# usb-lux-meter-v1.net
KiCad netlist of a schematic drawn in EAGLE
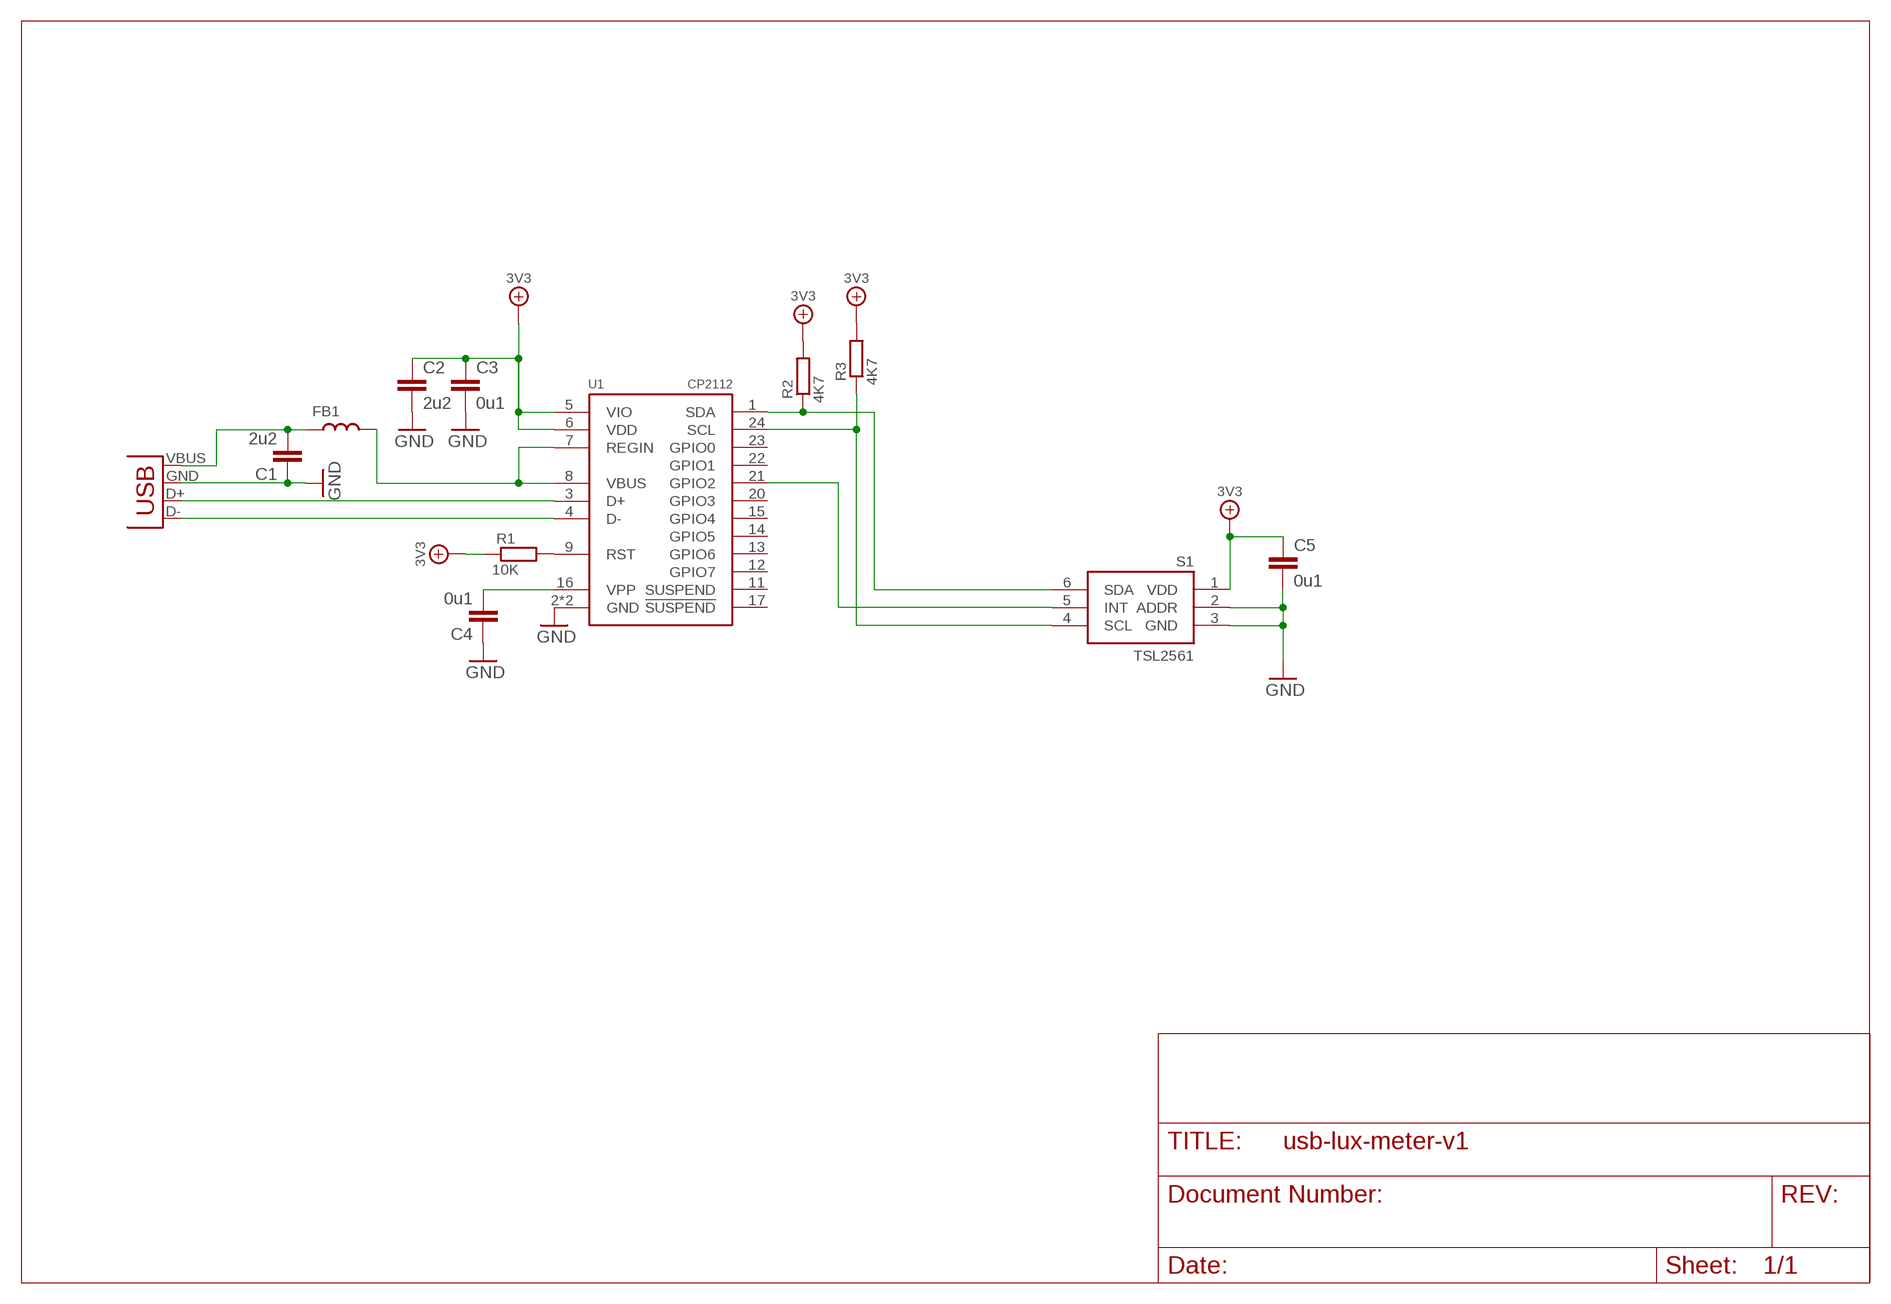
[diagram p0: schematic, sheet 1]

(export (version "E")
  (design (tool "Eeschema 10.0.6"))
  (components
    (comp (ref "C1")
      (value "2u2")
      (footprint "eagle-import:C0603")
      (libsource (lib "eagle-import") (part "CC0603"))
    )
    (comp (ref "C2")
      (value "2u2")
      (footprint "eagle-import:C0603")
      (libsource (lib "eagle-import") (part "CC0603"))
    )
    (comp (ref "C3")
      (value "0u1")
      (footprint "eagle-import:C0603")
      (libsource (lib "eagle-import") (part "CC0603"))
    )
    (comp (ref "C4")
      (value "0u1")
      (footprint "eagle-import:C0603")
      (libsource (lib "eagle-import") (part "CC0603"))
    )
    (comp (ref "C5")
      (value "0u1")
      (footprint "eagle-import:C0603")
      (libsource (lib "eagle-import") (part "CC0603"))
    )
    (comp (ref "CN1")
      (value "USB-A-H")
      (footprint "eagle-import:USB-A-H")
      (libsource (lib "eagle-import") (part "USB-A-H"))
    )
    (comp (ref "FB1")
      (value "L0603")
      (footprint "eagle-import:R603")
      (libsource (lib "eagle-import") (part "L0603"))
    )
    (comp (ref "R1")
      (value "10K")
      (footprint "eagle-import:R603")
      (libsource (lib "eagle-import") (part "RR603"))
    )
    (comp (ref "R2")
      (value "4K7")
      (footprint "eagle-import:R603")
      (libsource (lib "eagle-import") (part "RR603"))
    )
    (comp (ref "R3")
      (value "4K7")
      (footprint "eagle-import:R603")
      (libsource (lib "eagle-import") (part "RR603"))
    )
    (comp (ref "S1")
      (value "TSL2561")
      (footprint "eagle-import:TSL2561")
      (libsource (lib "eagle-import") (part "TSL2561"))
    )
    (comp (ref "U1")
      (value "CP2112")
      (footprint "eagle-import:QFN24")
      (libsource (lib "eagle-import") (part "CP2112"))
    )
  )
  (nets
    (net (code "1") (name "3V3") (class "Default")
      (node (ref "C2") (pin "1") (pinfunction "1_1") (pintype "passive"))
      (node (ref "C3") (pin "1") (pinfunction "1_1") (pintype "passive"))
      (node (ref "C5") (pin "1") (pinfunction "1_1") (pintype "passive"))
      (node (ref "R1") (pin "1") (pinfunction "1_1") (pintype "passive"))
      (node (ref "R2") (pin "2") (pinfunction "2_2") (pintype "passive"))
      (node (ref "R3") (pin "2") (pinfunction "2_2") (pintype "passive"))
      (node (ref "S1") (pin "1") (pinfunction "VDD_1") (pintype "bidirectional"))
      (node (ref "U1") (pin "5") (pinfunction "VIO_5") (pintype "bidirectional"))
      (node (ref "U1") (pin "6") (pinfunction "VDD_6") (pintype "bidirectional"))
    )
    (net (code "2") (name "GND") (class "Default")
      (node (ref "C1") (pin "1") (pinfunction "1_1") (pintype "passive"))
      (node (ref "C2") (pin "2") (pinfunction "2_2") (pintype "passive"))
      (node (ref "C3") (pin "2") (pinfunction "2_2") (pintype "passive"))
      (node (ref "C4") (pin "1") (pinfunction "1_1") (pintype "passive"))
      (node (ref "C5") (pin "2") (pinfunction "2_2") (pintype "passive"))
      (node (ref "CN1") (pin "GND") (pinfunction "VBUS_GND") (pintype "bidirectional"))
      (node (ref "S1") (pin "2") (pinfunction "ADDR_2") (pintype "bidirectional"))
      (node (ref "S1") (pin "3") (pinfunction "GND_3") (pintype "bidirectional"))
      (node (ref "U1") (pin "2") (pinfunction "GND_2") (pintype "bidirectional"))
      (node (ref "U1") (pin "GND") (pinfunction "GND_GND") (pintype "bidirectional"))
    )
    (net (code "3") (name "Net-(CN1-D+)") (class "Default")
      (node (ref "CN1") (pin "D-") (pinfunction "D+_D-") (pintype "bidirectional"))
      (node (ref "U1") (pin "4") (pinfunction "D-_4") (pintype "bidirectional"))
    )
    (net (code "4") (name "Net-(CN1-D-)") (class "Default")
      (node (ref "CN1") (pin "D+") (pinfunction "D-_D+") (pintype "bidirectional"))
      (node (ref "U1") (pin "3") (pinfunction "D+_3") (pintype "bidirectional"))
    )
    (net (code "5") (name "Net-(CN1-GND)") (class "Default")
      (node (ref "C1") (pin "2") (pinfunction "2_2") (pintype "passive"))
      (node (ref "CN1") (pin "VBUS") (pinfunction "GND_VBUS") (pintype "bidirectional"))
      (node (ref "FB1") (pin "1") (pinfunction "P$1_1") (pintype "bidirectional"))
    )
    (net (code "6") (name "Net-(FB1-P$2)") (class "Default")
      (node (ref "FB1") (pin "2") (pinfunction "P$2_2") (pintype "bidirectional"))
      (node (ref "U1") (pin "7") (pinfunction "REGIN_7") (pintype "bidirectional"))
      (node (ref "U1") (pin "8") (pinfunction "VBUS_8") (pintype "bidirectional"))
    )
    (net (code "7") (name "Net-(S1-INT)") (class "Default")
      (node (ref "S1") (pin "5") (pinfunction "INT_5") (pintype "bidirectional"))
      (node (ref "U1") (pin "21") (pinfunction "GPIO2_21") (pintype "bidirectional"))
    )
    (net (code "8") (name "Net-(S1-SCL)") (class "Default")
      (node (ref "R3") (pin "1") (pinfunction "1_1") (pintype "passive"))
      (node (ref "S1") (pin "4") (pinfunction "SCL_4") (pintype "bidirectional"))
      (node (ref "U1") (pin "24") (pinfunction "SCL_24") (pintype "bidirectional"))
    )
    (net (code "9") (name "Net-(S1-SDA)") (class "Default")
      (node (ref "R2") (pin "1") (pinfunction "1_1") (pintype "passive"))
      (node (ref "S1") (pin "6") (pinfunction "SDA_6") (pintype "bidirectional"))
      (node (ref "U1") (pin "1") (pinfunction "SDA_1") (pintype "bidirectional"))
    )
    (net (code "10") (name "Net-(U1-RST)") (class "Default")
      (node (ref "R1") (pin "2") (pinfunction "2_2") (pintype "passive"))
      (node (ref "U1") (pin "9") (pinfunction "RST_9") (pintype "bidirectional"))
    )
    (net (code "11") (name "Net-(U1-VPP)") (class "Default")
      (node (ref "C4") (pin "2") (pinfunction "2_2") (pintype "passive"))
      (node (ref "U1") (pin "16") (pinfunction "VPP_16") (pintype "bidirectional"))
    )
    (net (code "12") (name "unconnected-(U1-GPIO0-Pad23)") (class "Default")
      (node (ref "U1") (pin "23") (pinfunction "GPIO0_23") (pintype "bidirectional"))
    )
    (net (code "13") (name "unconnected-(U1-GPIO1-Pad22)") (class "Default")
      (node (ref "U1") (pin "22") (pinfunction "GPIO1_22") (pintype "bidirectional"))
    )
    (net (code "14") (name "unconnected-(U1-GPIO3-Pad20)") (class "Default")
      (node (ref "U1") (pin "20") (pinfunction "GPIO3_20") (pintype "bidirectional"))
    )
    (net (code "15") (name "unconnected-(U1-GPIO4-Pad15)") (class "Default")
      (node (ref "U1") (pin "15") (pinfunction "GPIO4_15") (pintype "bidirectional"))
    )
    (net (code "16") (name "unconnected-(U1-GPIO5-Pad14)") (class "Default")
      (node (ref "U1") (pin "14") (pinfunction "GPIO5_14") (pintype "bidirectional"))
    )
    (net (code "17") (name "unconnected-(U1-GPIO6-Pad13)") (class "Default")
      (node (ref "U1") (pin "13") (pinfunction "GPIO6_13") (pintype "bidirectional"))
    )
    (net (code "18") (name "unconnected-(U1-GPIO7-Pad12)") (class "Default")
      (node (ref "U1") (pin "12") (pinfunction "GPIO7_12") (pintype "bidirectional"))
    )
    (net (code "19") (name "unconnected-(U1-SUSPEND-Pad11)") (class "Default")
      (node (ref "U1") (pin "11") (pinfunction "SUSPEND_11") (pintype "bidirectional"))
    )
    (net (code "20") (name "unconnected-(U1-~{SUSPEND}-Pad17)") (class "Default")
      (node (ref "U1") (pin "17") (pinfunction "~{SUSPEND}_17") (pintype "bidirectional"))
    )
  )
)
